# tutorial.net
KiCad netlist of a schematic drawn in Altium Designer
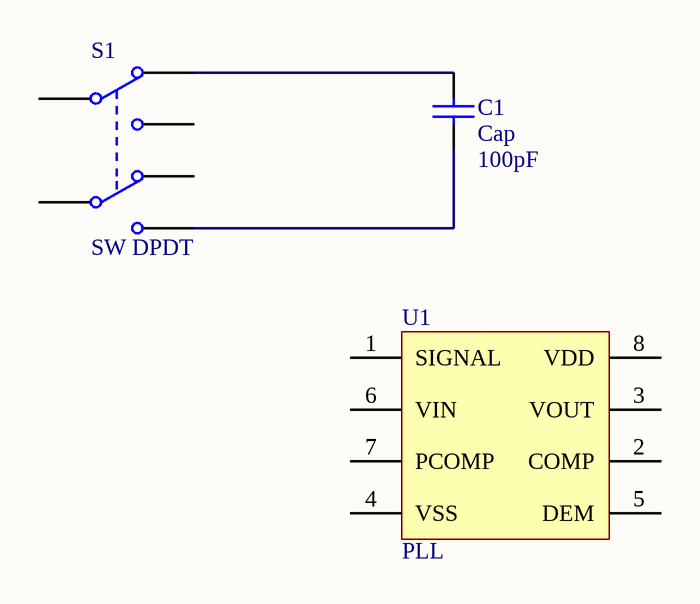
[diagram p0: tutorial.SchDoc]

(export (version "E")
  (design (tool "Eeschema 10.0.6"))
  (components
    (comp (ref "C1")
      (value "Cap")
      (footprint "RAD-0.3")
      (description "Capacitor")
      (fields (field (name "ALTIUM_VALUE") "100pF") (field (name "PUBLISHER") "Altium Limited"))
      (libsource (lib "Miscellaneous Devices") (part "Cap"))
    )
    (comp (ref "S1")
      (value "SW DPDT")
      (footprint "SOT23-6_L")
      (description "Switch")
      (fields (field (name "PUBLISHER") "Altium Limited"))
      (libsource (lib "Miscellaneous Devices") (part "SW DPDT"))
    )
    (comp (ref "U1")
      (value "PLL")
      (footprint "TSSOP-8")
      (description "Generic Phase Locked Loop")
      (fields (field (name "PUBLISHER") "Altium Limited"))
      (libsource (lib "Miscellaneous Devices") (part "PLL"))
    )
  )
  (nets
    (net (code "1") (name "Net-(S1-NC1)") (class "Default")
      (node (ref "C1") (pin "2") (pinfunction "2_2") (pintype "passive"))
      (node (ref "S1") (pin "2") (pinfunction "NC1_2") (pintype "passive"))
    )
    (net (code "2") (name "Net-(S1-NO2)") (class "Default")
      (node (ref "C1") (pin "1") (pinfunction "1_1") (pintype "passive"))
      (node (ref "S1") (pin "6") (pinfunction "NO2_6") (pintype "passive"))
    )
    (net (code "3") (name "unconnected-(S1-COMMON1-Pad1)") (class "Default")
      (node (ref "S1") (pin "1") (pinfunction "COMMON1_1") (pintype "passive"))
    )
    (net (code "4") (name "unconnected-(S1-COMMON2-Pad5)") (class "Default")
      (node (ref "S1") (pin "5") (pinfunction "COMMON2_5") (pintype "passive"))
    )
    (net (code "5") (name "unconnected-(S1-NC2-Pad4)") (class "Default")
      (node (ref "S1") (pin "4") (pinfunction "NC2_4") (pintype "passive"))
    )
    (net (code "6") (name "unconnected-(S1-NO1-Pad3)") (class "Default")
      (node (ref "S1") (pin "3") (pinfunction "NO1_3") (pintype "passive"))
    )
    (net (code "7") (name "unconnected-(U1-COMP-Pad2)") (class "Default")
      (node (ref "U1") (pin "2") (pinfunction "COMP_2") (pintype "passive"))
    )
    (net (code "8") (name "unconnected-(U1-DEM-Pad5)") (class "Default")
      (node (ref "U1") (pin "5") (pinfunction "DEM_5") (pintype "passive"))
    )
    (net (code "9") (name "unconnected-(U1-PCOMP-Pad7)") (class "Default")
      (node (ref "U1") (pin "7") (pinfunction "PCOMP_7") (pintype "passive"))
    )
    (net (code "10") (name "unconnected-(U1-SIGNAL-Pad1)") (class "Default")
      (node (ref "U1") (pin "1") (pinfunction "SIGNAL_1") (pintype "passive"))
    )
    (net (code "11") (name "unconnected-(U1-VDD-Pad8)") (class "Default")
      (node (ref "U1") (pin "8") (pinfunction "VDD_8") (pintype "passive"))
    )
    (net (code "12") (name "unconnected-(U1-VIN-Pad6)") (class "Default")
      (node (ref "U1") (pin "6") (pinfunction "VIN_6") (pintype "passive"))
    )
    (net (code "13") (name "unconnected-(U1-VOUT-Pad3)") (class "Default")
      (node (ref "U1") (pin "3") (pinfunction "VOUT_3") (pintype "passive"))
    )
    (net (code "14") (name "unconnected-(U1-VSS-Pad4)") (class "Default")
      (node (ref "U1") (pin "4") (pinfunction "VSS_4") (pintype "passive"))
    )
  )
)
